# Speedometer_Drive_Board.net
KiCad netlist of a schematic drawn in EAGLE
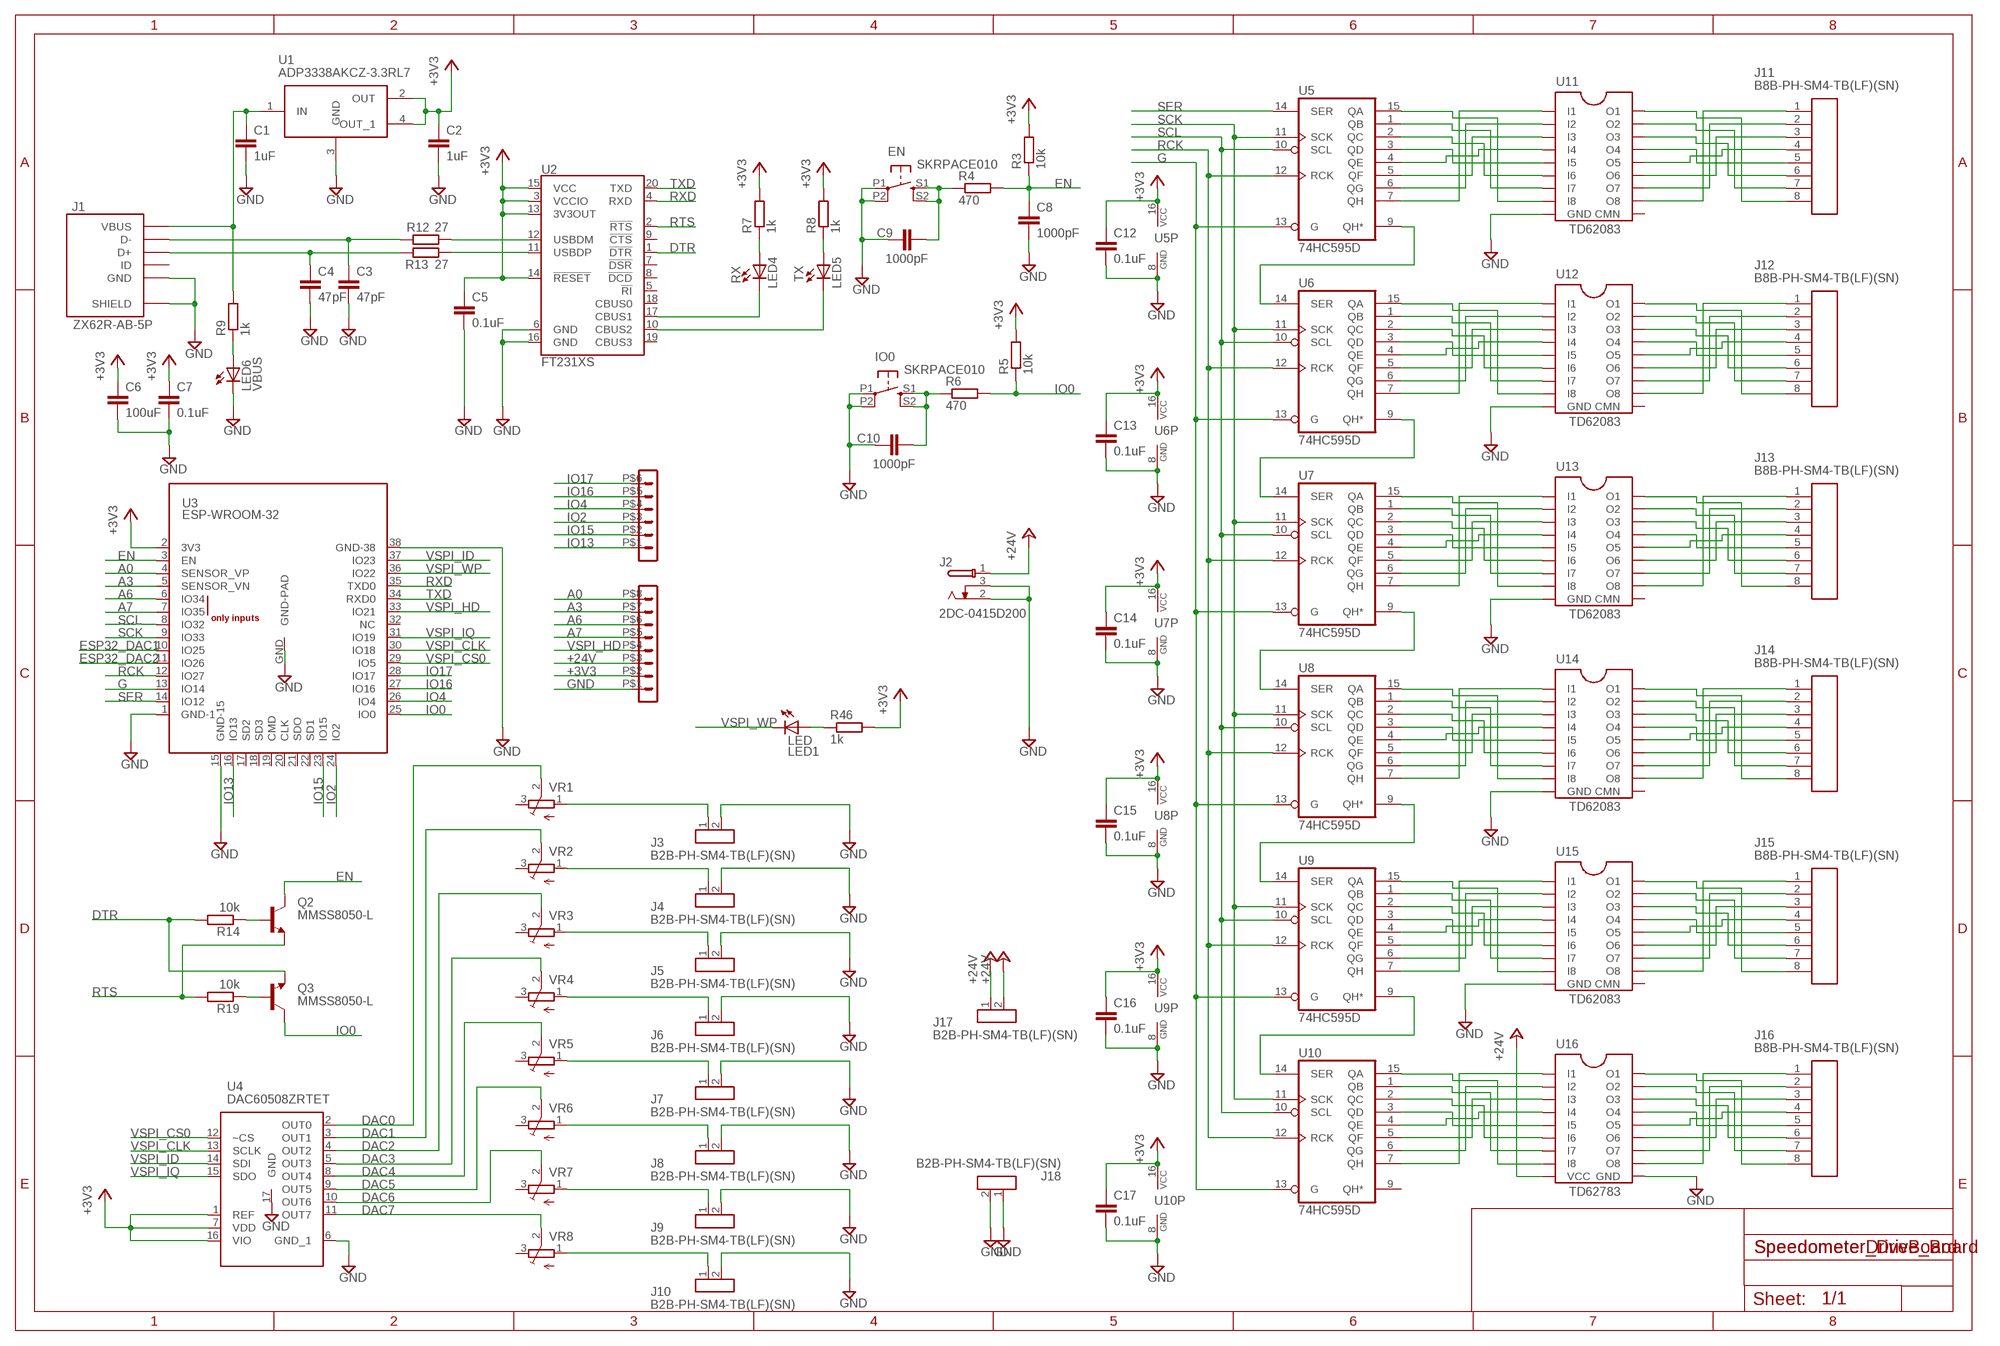
[diagram p0: schematic, sheet 1]

(export (version "E")
  (design (tool "Eeschema 10.0.6"))
  (components
    (comp (ref "C1")
      (value "1uF")
      (footprint "eagle-import:C0603")
      (libsource (lib "eagle-import") (part "C-EUC0603"))
    )
    (comp (ref "C2")
      (value "1uF")
      (footprint "eagle-import:C0603")
      (libsource (lib "eagle-import") (part "C-EUC0603"))
    )
    (comp (ref "C3")
      (value "47pF")
      (footprint "eagle-import:C0603")
      (libsource (lib "eagle-import") (part "C-EUC0603"))
    )
    (comp (ref "C4")
      (value "47pF")
      (footprint "eagle-import:C0603")
      (libsource (lib "eagle-import") (part "C-EUC0603"))
    )
    (comp (ref "C5")
      (value "0.1uF")
      (footprint "eagle-import:C0603")
      (libsource (lib "eagle-import") (part "C-EUC0603"))
    )
    (comp (ref "C6")
      (value "100uF")
      (footprint "eagle-import:C1210")
      (libsource (lib "eagle-import") (part "C-EUC1210"))
    )
    (comp (ref "C7")
      (value "0.1uF")
      (footprint "eagle-import:C0603")
      (libsource (lib "eagle-import") (part "C-EUC0603"))
    )
    (comp (ref "C8")
      (value "1000pF")
      (footprint "eagle-import:C0603")
      (libsource (lib "eagle-import") (part "C-EUC0603"))
    )
    (comp (ref "C9")
      (value "1000pF")
      (footprint "eagle-import:C0603")
      (libsource (lib "eagle-import") (part "C-EUC0603"))
    )
    (comp (ref "C10")
      (value "1000pF")
      (footprint "eagle-import:C0603")
      (libsource (lib "eagle-import") (part "C-EUC0603"))
    )
    (comp (ref "C12")
      (value "0.1uF")
      (footprint "eagle-import:C0603")
      (libsource (lib "eagle-import") (part "C-EUC0603"))
    )
    (comp (ref "C13")
      (value "0.1uF")
      (footprint "eagle-import:C0603")
      (libsource (lib "eagle-import") (part "C-EUC0603"))
    )
    (comp (ref "C14")
      (value "0.1uF")
      (footprint "eagle-import:C0603")
      (libsource (lib "eagle-import") (part "C-EUC0603"))
    )
    (comp (ref "C15")
      (value "0.1uF")
      (footprint "eagle-import:C0603")
      (libsource (lib "eagle-import") (part "C-EUC0603"))
    )
    (comp (ref "C16")
      (value "0.1uF")
      (footprint "eagle-import:C0603")
      (libsource (lib "eagle-import") (part "C-EUC0603"))
    )
    (comp (ref "C17")
      (value "0.1uF")
      (footprint "eagle-import:C0603")
      (libsource (lib "eagle-import") (part "C-EUC0603"))
    )
    (comp (ref "EN")
      (value "SKRPACE010")
      (footprint "eagle-import:SKRPACE010")
      (libsource (lib "eagle-import") (part "SKRPACE010"))
    )
    (comp (ref "IO0")
      (value "SKRPACE010")
      (footprint "eagle-import:SKRPACE010")
      (libsource (lib "eagle-import") (part "SKRPACE010"))
    )
    (comp (ref "J1")
      (value "ZX62R-AB-5P")
      (footprint "eagle-import:ZX62R-B-5PA")
      (libsource (lib "eagle-import") (part "ZX62R-AB-5P"))
    )
    (comp (ref "J2")
      (value "2DC-0415D200")
      (footprint "eagle-import:2DC-0415D200")
      (libsource (lib "eagle-import") (part "2DC-0415D200"))
    )
    (comp (ref "J3")
      (value "B2B-PH-SM4-TB(LF)(SN)")
      (footprint "eagle-import:SAMACSYS_PARTS_B2B-PH-SM4-TB")
      (fields (field (name "RS_PART_NUMBER") "6881325P"))
      (libsource (lib "eagle-import") (part "B2B-PH-SM4-TB(LF)(SN)"))
    )
    (comp (ref "J4")
      (value "B2B-PH-SM4-TB(LF)(SN)")
      (footprint "eagle-import:SAMACSYS_PARTS_B2B-PH-SM4-TB")
      (fields (field (name "RS_PART_NUMBER") "6881325P"))
      (libsource (lib "eagle-import") (part "B2B-PH-SM4-TB(LF)(SN)"))
    )
    (comp (ref "J5")
      (value "B2B-PH-SM4-TB(LF)(SN)")
      (footprint "eagle-import:SAMACSYS_PARTS_B2B-PH-SM4-TB")
      (fields (field (name "RS_PART_NUMBER") "6881325P"))
      (libsource (lib "eagle-import") (part "B2B-PH-SM4-TB(LF)(SN)"))
    )
    (comp (ref "J6")
      (value "B2B-PH-SM4-TB(LF)(SN)")
      (footprint "eagle-import:SAMACSYS_PARTS_B2B-PH-SM4-TB")
      (fields (field (name "RS_PART_NUMBER") "6881325P"))
      (libsource (lib "eagle-import") (part "B2B-PH-SM4-TB(LF)(SN)"))
    )
    (comp (ref "J7")
      (value "B2B-PH-SM4-TB(LF)(SN)")
      (footprint "eagle-import:SAMACSYS_PARTS_B2B-PH-SM4-TB")
      (fields (field (name "RS_PART_NUMBER") "6881325P"))
      (libsource (lib "eagle-import") (part "B2B-PH-SM4-TB(LF)(SN)"))
    )
    (comp (ref "J8")
      (value "B2B-PH-SM4-TB(LF)(SN)")
      (footprint "eagle-import:SAMACSYS_PARTS_B2B-PH-SM4-TB")
      (fields (field (name "RS_PART_NUMBER") "6881325P"))
      (libsource (lib "eagle-import") (part "B2B-PH-SM4-TB(LF)(SN)"))
    )
    (comp (ref "J9")
      (value "B2B-PH-SM4-TB(LF)(SN)")
      (footprint "eagle-import:SAMACSYS_PARTS_B2B-PH-SM4-TB")
      (fields (field (name "RS_PART_NUMBER") "6881325P"))
      (libsource (lib "eagle-import") (part "B2B-PH-SM4-TB(LF)(SN)"))
    )
    (comp (ref "J10")
      (value "B2B-PH-SM4-TB(LF)(SN)")
      (footprint "eagle-import:SAMACSYS_PARTS_B2B-PH-SM4-TB")
      (fields (field (name "RS_PART_NUMBER") "6881325P"))
      (libsource (lib "eagle-import") (part "B2B-PH-SM4-TB(LF)(SN)"))
    )
    (comp (ref "J11")
      (value "B8B-PH-SM4-TB(LF)(SN)")
      (footprint "eagle-import:SAMACSYS_PARTS_B8B-PH-SM4-TB")
      (fields (field (name "RS_PART_NUMBER") "1667263"))
      (libsource (lib "eagle-import") (part "B8B-PH-SM4-TB(LF)(SN)"))
    )
    (comp (ref "J12")
      (value "B8B-PH-SM4-TB(LF)(SN)")
      (footprint "eagle-import:SAMACSYS_PARTS_B8B-PH-SM4-TB")
      (fields (field (name "RS_PART_NUMBER") "1667263"))
      (libsource (lib "eagle-import") (part "B8B-PH-SM4-TB(LF)(SN)"))
    )
    (comp (ref "J13")
      (value "B8B-PH-SM4-TB(LF)(SN)")
      (footprint "eagle-import:SAMACSYS_PARTS_B8B-PH-SM4-TB")
      (fields (field (name "RS_PART_NUMBER") "1667263"))
      (libsource (lib "eagle-import") (part "B8B-PH-SM4-TB(LF)(SN)"))
    )
    (comp (ref "J14")
      (value "B8B-PH-SM4-TB(LF)(SN)")
      (footprint "eagle-import:SAMACSYS_PARTS_B8B-PH-SM4-TB")
      (fields (field (name "RS_PART_NUMBER") "1667263"))
      (libsource (lib "eagle-import") (part "B8B-PH-SM4-TB(LF)(SN)"))
    )
    (comp (ref "J15")
      (value "B8B-PH-SM4-TB(LF)(SN)")
      (footprint "eagle-import:SAMACSYS_PARTS_B8B-PH-SM4-TB")
      (fields (field (name "RS_PART_NUMBER") "1667263"))
      (libsource (lib "eagle-import") (part "B8B-PH-SM4-TB(LF)(SN)"))
    )
    (comp (ref "J16")
      (value "B8B-PH-SM4-TB(LF)(SN)")
      (footprint "eagle-import:SAMACSYS_PARTS_B8B-PH-SM4-TB")
      (fields (field (name "RS_PART_NUMBER") "1667263"))
      (libsource (lib "eagle-import") (part "B8B-PH-SM4-TB(LF)(SN)"))
    )
    (comp (ref "J17")
      (value "B2B-PH-SM4-TB(LF)(SN)")
      (footprint "eagle-import:SAMACSYS_PARTS_B2B-PH-SM4-TB")
      (fields (field (name "RS_PART_NUMBER") "6881325P"))
      (libsource (lib "eagle-import") (part "B2B-PH-SM4-TB(LF)(SN)"))
    )
    (comp (ref "J18")
      (value "B2B-PH-SM4-TB(LF)(SN)")
      (footprint "eagle-import:SAMACSYS_PARTS_B2B-PH-SM4-TB")
      (fields (field (name "RS_PART_NUMBER") "6881325P"))
      (libsource (lib "eagle-import") (part "B2B-PH-SM4-TB(LF)(SN)"))
    )
    (comp (ref "J19")
      (value "PIN_HEADER_MALE_1X06_06P")
      (footprint "eagle-import:PIN_HEADER_MALE_1X06_06P")
      (libsource (lib "eagle-import") (part "PIN_HEADER_MALE_1X06_06P"))
    )
    (comp (ref "J20")
      (value "PIN_HEADER_MALE_1X08_08P")
      (footprint "eagle-import:PIN_HEADER_MALE_1X08_08P")
      (libsource (lib "eagle-import") (part "PIN_HEADER_MALE_1X08_08P"))
    )
    (comp (ref "LED")
      (value "LED1")
      (footprint "eagle-import:CHIPLED_0603")
      (libsource (lib "eagle-import") (part "LEDCHIPLED_0603"))
    )
    (comp (ref "LED4")
      (value "RX")
      (footprint "eagle-import:CHIPLED_0603")
      (libsource (lib "eagle-import") (part "LEDCHIPLED_0603"))
    )
    (comp (ref "LED5")
      (value "TX")
      (footprint "eagle-import:CHIPLED_0603")
      (libsource (lib "eagle-import") (part "LEDCHIPLED_0603"))
    )
    (comp (ref "LED6")
      (value "VBUS")
      (footprint "eagle-import:CHIPLED_0603")
      (libsource (lib "eagle-import") (part "LEDCHIPLED_0603"))
    )
    (comp (ref "Q2")
      (value "MMSS8050-L")
      (footprint "eagle-import:SOT23")
      (libsource (lib "eagle-import") (part "MMSS8050-L"))
    )
    (comp (ref "Q3")
      (value "MMSS8050-L")
      (footprint "eagle-import:SOT23")
      (libsource (lib "eagle-import") (part "MMSS8050-L"))
    )
    (comp (ref "R3")
      (value "10k")
      (footprint "eagle-import:R0603")
      (libsource (lib "eagle-import") (part "R-EU_R0603"))
    )
    (comp (ref "R4")
      (value "470")
      (footprint "eagle-import:R0603")
      (libsource (lib "eagle-import") (part "R-EU_R0603"))
    )
    (comp (ref "R5")
      (value "10k")
      (footprint "eagle-import:R0603")
      (libsource (lib "eagle-import") (part "R-EU_R0603"))
    )
    (comp (ref "R6")
      (value "470")
      (footprint "eagle-import:R0603")
      (libsource (lib "eagle-import") (part "R-EU_R0603"))
    )
    (comp (ref "R7")
      (value "1k")
      (footprint "eagle-import:R0603")
      (libsource (lib "eagle-import") (part "R-EU_R0603"))
    )
    (comp (ref "R8")
      (value "1k")
      (footprint "eagle-import:R0603")
      (libsource (lib "eagle-import") (part "R-EU_R0603"))
    )
    (comp (ref "R9")
      (value "1k")
      (footprint "eagle-import:R0603")
      (libsource (lib "eagle-import") (part "R-EU_R0603"))
    )
    (comp (ref "R12")
      (value "27")
      (footprint "eagle-import:R0603")
      (libsource (lib "eagle-import") (part "R-EU_R0603"))
    )
    (comp (ref "R13")
      (value "27")
      (footprint "eagle-import:R0603")
      (libsource (lib "eagle-import") (part "R-EU_R0603"))
    )
    (comp (ref "R14")
      (value "10k")
      (footprint "eagle-import:R0603")
      (libsource (lib "eagle-import") (part "R-EU_R0603"))
    )
    (comp (ref "R19")
      (value "10k")
      (footprint "eagle-import:R0603")
      (libsource (lib "eagle-import") (part "R-EU_R0603"))
    )
    (comp (ref "R46")
      (value "1k")
      (footprint "eagle-import:R0603")
      (libsource (lib "eagle-import") (part "R-EU_R0603"))
    )
    (comp (ref "U1")
      (value "ADP3338AKCZ-3.3RL7")
      (footprint "eagle-import:SOT230P700X180-4N")
      (fields (field (name "RS_PART_NUMBER") "9126350"))
      (libsource (lib "eagle-import") (part "ADP3338AKCZ-3.3RL7"))
    )
    (comp (ref "U2")
      (value "FT231XS")
      (footprint "eagle-import:SSOP20_L")
      (libsource (lib "eagle-import") (part "FT231XS"))
    )
    (comp (ref "U3")
      (value "ESP-WROOM-32")
      (footprint "eagle-import:ESP-WROOM-32")
      (libsource (lib "eagle-import") (part "ESP-WROOM-32"))
    )
    (comp (ref "U4")
      (value "DAC60508ZRTET")
      (footprint "eagle-import:SAMACSYS_PARTS_QFN50P300X300X80-17N")
      (fields (field (name "MOUSER_PART_NUMBER") "595-DAC60508ZRTET"))
      (libsource (lib "eagle-import") (part "DAC60508ZRTET"))
    )
    (comp (ref "U5")
      (value "74HC595D")
      (footprint "eagle-import:SO16")
      (libsource (lib "eagle-import") (part "74595DHC"))
    )
    (comp (ref "U6")
      (value "74HC595D")
      (footprint "eagle-import:SO16")
      (libsource (lib "eagle-import") (part "74595DHC"))
    )
    (comp (ref "U7")
      (value "74HC595D")
      (footprint "eagle-import:SO16")
      (libsource (lib "eagle-import") (part "74595DHC"))
    )
    (comp (ref "U8")
      (value "74HC595D")
      (footprint "eagle-import:SO16")
      (libsource (lib "eagle-import") (part "74595DHC"))
    )
    (comp (ref "U9")
      (value "74HC595D")
      (footprint "eagle-import:SO16")
      (libsource (lib "eagle-import") (part "74595DHC"))
    )
    (comp (ref "U10")
      (value "74HC595D")
      (footprint "eagle-import:SO16")
      (libsource (lib "eagle-import") (part "74595DHC"))
    )
    (comp (ref "U11")
      (value "TD62083")
      (footprint "eagle-import:SO18")
      (libsource (lib "eagle-import") (part "TD62083"))
    )
    (comp (ref "U12")
      (value "TD62083")
      (footprint "eagle-import:SO18")
      (libsource (lib "eagle-import") (part "TD62083"))
    )
    (comp (ref "U13")
      (value "TD62083")
      (footprint "eagle-import:SO18")
      (libsource (lib "eagle-import") (part "TD62083"))
    )
    (comp (ref "U14")
      (value "TD62083")
      (footprint "eagle-import:SO18")
      (libsource (lib "eagle-import") (part "TD62083"))
    )
    (comp (ref "U15")
      (value "TD62083")
      (footprint "eagle-import:SO18")
      (libsource (lib "eagle-import") (part "TD62083"))
    )
    (comp (ref "U16")
      (value "TD62783")
      (footprint "eagle-import:SO18")
      (libsource (lib "eagle-import") (part "TD62783"))
    )
    (comp (ref "VR1")
      (value "TRIM_EU-SM-42/43W")
      (footprint "eagle-import:SM-42_43W")
      (libsource (lib "eagle-import") (part "TRIM_EU-SM-42/43W"))
    )
    (comp (ref "VR2")
      (value "TRIM_EU-SM-42/43W")
      (footprint "eagle-import:SM-42_43W")
      (libsource (lib "eagle-import") (part "TRIM_EU-SM-42/43W"))
    )
    (comp (ref "VR3")
      (value "TRIM_EU-SM-42/43W")
      (footprint "eagle-import:SM-42_43W")
      (libsource (lib "eagle-import") (part "TRIM_EU-SM-42/43W"))
    )
    (comp (ref "VR4")
      (value "TRIM_EU-SM-42/43W")
      (footprint "eagle-import:SM-42_43W")
      (libsource (lib "eagle-import") (part "TRIM_EU-SM-42/43W"))
    )
    (comp (ref "VR5")
      (value "TRIM_EU-SM-42/43W")
      (footprint "eagle-import:SM-42_43W")
      (libsource (lib "eagle-import") (part "TRIM_EU-SM-42/43W"))
    )
    (comp (ref "VR6")
      (value "TRIM_EU-SM-42/43W")
      (footprint "eagle-import:SM-42_43W")
      (libsource (lib "eagle-import") (part "TRIM_EU-SM-42/43W"))
    )
    (comp (ref "VR7")
      (value "TRIM_EU-SM-42/43W")
      (footprint "eagle-import:SM-42_43W")
      (libsource (lib "eagle-import") (part "TRIM_EU-SM-42/43W"))
    )
    (comp (ref "VR8")
      (value "TRIM_EU-SM-42/43W")
      (footprint "eagle-import:SM-42_43W")
      (libsource (lib "eagle-import") (part "TRIM_EU-SM-42/43W"))
    )
  )
  (nets
    (net (code "1") (name "+3V3") (class "Default")
      (node (ref "C12") (pin "1") (pinfunction "1_1") (pintype "passive"))
      (node (ref "C13") (pin "1") (pinfunction "1_1") (pintype "passive"))
      (node (ref "C14") (pin "1") (pinfunction "1_1") (pintype "passive"))
      (node (ref "C15") (pin "1") (pinfunction "1_1") (pintype "passive"))
      (node (ref "C16") (pin "1") (pinfunction "1_1") (pintype "passive"))
      (node (ref "C17") (pin "1") (pinfunction "1_1") (pintype "passive"))
      (node (ref "C2") (pin "1") (pinfunction "1_1") (pintype "passive"))
      (node (ref "C5") (pin "1") (pinfunction "1_1") (pintype "passive"))
      (node (ref "C6") (pin "1") (pinfunction "1_1") (pintype "passive"))
      (node (ref "C7") (pin "1") (pinfunction "1_1") (pintype "passive"))
      (node (ref "J20") (pin "P$2") (pinfunction "2_P$2") (pintype "bidirectional"))
      (node (ref "R3") (pin "2") (pinfunction "2_2") (pintype "passive"))
      (node (ref "R46") (pin "2") (pinfunction "2_2") (pintype "passive"))
      (node (ref "R5") (pin "2") (pinfunction "2_2") (pintype "passive"))
      (node (ref "R7") (pin "2") (pinfunction "2_2") (pintype "passive"))
      (node (ref "R8") (pin "2") (pinfunction "2_2") (pintype "passive"))
      (node (ref "U1") (pin "2") (pinfunction "OUT_2") (pintype "output"))
      (node (ref "U1") (pin "4") (pinfunction "OUT_1_4") (pintype "output"))
      (node (ref "U10") (pin "16") (pinfunction "VCC_16") (pintype "power_in"))
      (node (ref "U2") (pin "13") (pinfunction "3V3OUT_13") (pintype "bidirectional"))
      (node (ref "U2") (pin "14") (pinfunction "~{RESET}_14") (pintype "bidirectional"))
      (node (ref "U2") (pin "15") (pinfunction "VCC_15") (pintype "bidirectional"))
      (node (ref "U2") (pin "3") (pinfunction "VCCIO_3") (pintype "bidirectional"))
      (node (ref "U3") (pin "2") (pinfunction "3V3_2") (pintype "bidirectional"))
      (node (ref "U4") (pin "1") (pinfunction "REF_1") (pintype "bidirectional"))
      (node (ref "U4") (pin "16") (pinfunction "VIO_16") (pintype "bidirectional"))
      (node (ref "U4") (pin "7") (pinfunction "VDD_7") (pintype "bidirectional"))
      (node (ref "U5") (pin "16") (pinfunction "VCC_16") (pintype "power_in"))
      (node (ref "U6") (pin "16") (pinfunction "VCC_16") (pintype "power_in"))
      (node (ref "U7") (pin "16") (pinfunction "VCC_16") (pintype "power_in"))
      (node (ref "U8") (pin "16") (pinfunction "VCC_16") (pintype "power_in"))
      (node (ref "U9") (pin "16") (pinfunction "VCC_16") (pintype "power_in"))
    )
    (net (code "2") (name "+24V") (class "Default")
      (node (ref "J17") (pin "1") (pinfunction "P$1_1") (pintype "bidirectional"))
      (node (ref "J17") (pin "2") (pinfunction "P$2_2") (pintype "bidirectional"))
      (node (ref "J2") (pin "1") (pinfunction "1_1") (pintype "passive"))
      (node (ref "J20") (pin "P$3") (pinfunction "3_P$3") (pintype "bidirectional"))
      (node (ref "U16") (pin "9") (pinfunction "VCC_9") (pintype "passive"))
    )
    (net (code "3") (name "/A0") (class "Default")
      (node (ref "J20") (pin "P$8") (pinfunction "8_P$8") (pintype "bidirectional"))
      (node (ref "U3") (pin "4") (pinfunction "SENSOR_VP_4") (pintype "input"))
    )
    (net (code "4") (name "/A3") (class "Default")
      (node (ref "J20") (pin "P$7") (pinfunction "7_P$7") (pintype "bidirectional"))
      (node (ref "U3") (pin "5") (pinfunction "SENSOR_VN_5") (pintype "input"))
    )
    (net (code "5") (name "/A6") (class "Default")
      (node (ref "J20") (pin "P$6") (pinfunction "6_P$6") (pintype "bidirectional"))
      (node (ref "U3") (pin "6") (pinfunction "IO34_6") (pintype "input"))
    )
    (net (code "6") (name "/A7") (class "Default")
      (node (ref "J20") (pin "P$5") (pinfunction "5_P$5") (pintype "bidirectional"))
      (node (ref "U3") (pin "7") (pinfunction "IO35_7") (pintype "input"))
    )
    (net (code "7") (name "/DAC0") (class "Default")
      (node (ref "U4") (pin "2") (pinfunction "OUT0_2") (pintype "bidirectional"))
      (node (ref "VR1") (pin "2") (pinfunction "S_2") (pintype "passive"))
    )
    (net (code "8") (name "/DAC1") (class "Default")
      (node (ref "U4") (pin "3") (pinfunction "OUT1_3") (pintype "bidirectional"))
      (node (ref "VR2") (pin "2") (pinfunction "S_2") (pintype "passive"))
    )
    (net (code "9") (name "/DAC2") (class "Default")
      (node (ref "U4") (pin "4") (pinfunction "OUT2_4") (pintype "bidirectional"))
      (node (ref "VR3") (pin "2") (pinfunction "S_2") (pintype "passive"))
    )
    (net (code "10") (name "/DAC3") (class "Default")
      (node (ref "U4") (pin "5") (pinfunction "OUT3_5") (pintype "bidirectional"))
      (node (ref "VR4") (pin "2") (pinfunction "S_2") (pintype "passive"))
    )
    (net (code "11") (name "/DAC4") (class "Default")
      (node (ref "U4") (pin "8") (pinfunction "OUT4_8") (pintype "bidirectional"))
      (node (ref "VR5") (pin "2") (pinfunction "S_2") (pintype "passive"))
    )
    (net (code "12") (name "/DAC5") (class "Default")
      (node (ref "U4") (pin "9") (pinfunction "OUT5_9") (pintype "bidirectional"))
      (node (ref "VR6") (pin "2") (pinfunction "S_2") (pintype "passive"))
    )
    (net (code "13") (name "/DAC6") (class "Default")
      (node (ref "U4") (pin "10") (pinfunction "OUT6_10") (pintype "bidirectional"))
      (node (ref "VR7") (pin "2") (pinfunction "S_2") (pintype "passive"))
    )
    (net (code "14") (name "/DAC7") (class "Default")
      (node (ref "U4") (pin "11") (pinfunction "OUT7_11") (pintype "bidirectional"))
      (node (ref "VR8") (pin "2") (pinfunction "S_2") (pintype "passive"))
    )
    (net (code "15") (name "/DTR") (class "Default")
      (node (ref "Q3") (pin "E") (pinfunction "E_E") (pintype "passive"))
      (node (ref "R14") (pin "2") (pinfunction "2_2") (pintype "passive"))
      (node (ref "U2") (pin "1") (pinfunction "~{DTR}_1") (pintype "bidirectional"))
    )
    (net (code "16") (name "/EN") (class "Default")
      (node (ref "C8") (pin "1") (pinfunction "1_1") (pintype "passive"))
      (node (ref "Q2") (pin "C") (pinfunction "C_C") (pintype "passive"))
      (node (ref "R3") (pin "1") (pinfunction "1_1") (pintype "passive"))
      (node (ref "R4") (pin "2") (pinfunction "2_2") (pintype "passive"))
      (node (ref "U3") (pin "3") (pinfunction "EN_3") (pintype "bidirectional"))
    )
    (net (code "17") (name "/ESP32_DAC1") (class "Default")
      (node (ref "U3") (pin "10") (pinfunction "IO25_10") (pintype "bidirectional"))
    )
    (net (code "18") (name "/ESP32_DAC2") (class "Default")
      (node (ref "U3") (pin "11") (pinfunction "IO26_11") (pintype "bidirectional"))
    )
    (net (code "19") (name "/G") (class "Default")
      (node (ref "U10") (pin "13") (pinfunction "G_13") (pintype "input"))
      (node (ref "U3") (pin "13") (pinfunction "IO14_13") (pintype "bidirectional"))
      (node (ref "U5") (pin "13") (pinfunction "G_13") (pintype "input"))
      (node (ref "U6") (pin "13") (pinfunction "G_13") (pintype "input"))
      (node (ref "U7") (pin "13") (pinfunction "G_13") (pintype "input"))
      (node (ref "U8") (pin "13") (pinfunction "G_13") (pintype "input"))
      (node (ref "U9") (pin "13") (pinfunction "G_13") (pintype "input"))
    )
    (net (code "20") (name "/IO0") (class "Default")
      (node (ref "Q3") (pin "C") (pinfunction "C_C") (pintype "passive"))
      (node (ref "R5") (pin "1") (pinfunction "1_1") (pintype "passive"))
      (node (ref "R6") (pin "2") (pinfunction "2_2") (pintype "passive"))
      (node (ref "U3") (pin "25") (pinfunction "IO0_25") (pintype "bidirectional"))
    )
    (net (code "21") (name "/IO2") (class "Default")
      (node (ref "J19") (pin "P$3") (pinfunction "3_P$3") (pintype "bidirectional"))
      (node (ref "U3") (pin "24") (pinfunction "IO2_24") (pintype "bidirectional"))
    )
    (net (code "22") (name "/IO4") (class "Default")
      (node (ref "J19") (pin "P$4") (pinfunction "4_P$4") (pintype "bidirectional"))
      (node (ref "U3") (pin "26") (pinfunction "IO4_26") (pintype "bidirectional"))
    )
    (net (code "23") (name "/IO13") (class "Default")
      (node (ref "J19") (pin "P$1") (pinfunction "1_P$1") (pintype "bidirectional"))
      (node (ref "U3") (pin "16") (pinfunction "IO13_16") (pintype "bidirectional"))
    )
    (net (code "24") (name "/IO15") (class "Default")
      (node (ref "J19") (pin "P$2") (pinfunction "2_P$2") (pintype "bidirectional"))
      (node (ref "U3") (pin "23") (pinfunction "IO15_23") (pintype "bidirectional"))
    )
    (net (code "25") (name "/IO16") (class "Default")
      (node (ref "J19") (pin "P$5") (pinfunction "5_P$5") (pintype "bidirectional"))
      (node (ref "U3") (pin "27") (pinfunction "IO16_27") (pintype "bidirectional"))
    )
    (net (code "26") (name "/IO17") (class "Default")
      (node (ref "J19") (pin "P$6") (pinfunction "6_P$6") (pintype "bidirectional"))
      (node (ref "U3") (pin "28") (pinfunction "IO17_28") (pintype "bidirectional"))
    )
    (net (code "27") (name "/RCK") (class "Default")
      (node (ref "U10") (pin "12") (pinfunction "RCK_12") (pintype "input"))
      (node (ref "U3") (pin "12") (pinfunction "IO27_12") (pintype "bidirectional"))
      (node (ref "U5") (pin "12") (pinfunction "RCK_12") (pintype "input"))
      (node (ref "U6") (pin "12") (pinfunction "RCK_12") (pintype "input"))
      (node (ref "U7") (pin "12") (pinfunction "RCK_12") (pintype "input"))
      (node (ref "U8") (pin "12") (pinfunction "RCK_12") (pintype "input"))
      (node (ref "U9") (pin "12") (pinfunction "RCK_12") (pintype "input"))
    )
    (net (code "28") (name "/RTS") (class "Default")
      (node (ref "Q2") (pin "E") (pinfunction "E_E") (pintype "passive"))
      (node (ref "R19") (pin "2") (pinfunction "2_2") (pintype "passive"))
      (node (ref "U2") (pin "2") (pinfunction "~{RTS}_2") (pintype "bidirectional"))
    )
    (net (code "29") (name "/RXD") (class "Default")
      (node (ref "U2") (pin "4") (pinfunction "RXD_4") (pintype "bidirectional"))
      (node (ref "U3") (pin "35") (pinfunction "TXD0_35") (pintype "bidirectional"))
    )
    (net (code "30") (name "/SCK") (class "Default")
      (node (ref "U10") (pin "11") (pinfunction "SCK_11") (pintype "input"))
      (node (ref "U3") (pin "9") (pinfunction "IO33_9") (pintype "bidirectional"))
      (node (ref "U5") (pin "11") (pinfunction "SCK_11") (pintype "input"))
      (node (ref "U6") (pin "11") (pinfunction "SCK_11") (pintype "input"))
      (node (ref "U7") (pin "11") (pinfunction "SCK_11") (pintype "input"))
      (node (ref "U8") (pin "11") (pinfunction "SCK_11") (pintype "input"))
      (node (ref "U9") (pin "11") (pinfunction "SCK_11") (pintype "input"))
    )
    (net (code "31") (name "/SCL") (class "Default")
      (node (ref "U10") (pin "10") (pinfunction "SCL_10") (pintype "input"))
      (node (ref "U3") (pin "8") (pinfunction "IO32_8") (pintype "bidirectional"))
      (node (ref "U5") (pin "10") (pinfunction "SCL_10") (pintype "input"))
      (node (ref "U6") (pin "10") (pinfunction "SCL_10") (pintype "input"))
      (node (ref "U7") (pin "10") (pinfunction "SCL_10") (pintype "input"))
      (node (ref "U8") (pin "10") (pinfunction "SCL_10") (pintype "input"))
      (node (ref "U9") (pin "10") (pinfunction "SCL_10") (pintype "input"))
    )
    (net (code "32") (name "/SER") (class "Default")
      (node (ref "U3") (pin "14") (pinfunction "IO12_14") (pintype "bidirectional"))
      (node (ref "U5") (pin "14") (pinfunction "SER_14") (pintype "input"))
    )
    (net (code "33") (name "/TXD") (class "Default")
      (node (ref "U2") (pin "20") (pinfunction "TXD_20") (pintype "bidirectional"))
      (node (ref "U3") (pin "34") (pinfunction "RXD0_34") (pintype "bidirectional"))
    )
    (net (code "34") (name "/VSPI_CLK") (class "Default")
      (node (ref "U3") (pin "30") (pinfunction "IO18_30") (pintype "bidirectional"))
      (node (ref "U4") (pin "13") (pinfunction "SCLK_13") (pintype "bidirectional"))
    )
    (net (code "35") (name "/VSPI_CS0") (class "Default")
      (node (ref "U3") (pin "29") (pinfunction "IO5_29") (pintype "bidirectional"))
      (node (ref "U4") (pin "12") (pinfunction "~{CS}_12") (pintype "bidirectional"))
    )
    (net (code "36") (name "/VSPI_HD") (class "Default")
      (node (ref "J20") (pin "P$4") (pinfunction "4_P$4") (pintype "bidirectional"))
      (node (ref "U3") (pin "33") (pinfunction "IO21_33") (pintype "bidirectional"))
    )
    (net (code "37") (name "/VSPI_ID") (class "Default")
      (node (ref "U3") (pin "37") (pinfunction "IO23_37") (pintype "bidirectional"))
      (node (ref "U4") (pin "14") (pinfunction "SDI_14") (pintype "bidirectional"))
    )
    (net (code "38") (name "/VSPI_IQ") (class "Default")
      (node (ref "U3") (pin "31") (pinfunction "IO19_31") (pintype "bidirectional"))
      (node (ref "U4") (pin "15") (pinfunction "SDO_15") (pintype "bidirectional"))
    )
    (net (code "39") (name "/VSPI_WP") (class "Default")
      (node (ref "LED") (pin "C") (pinfunction "C_C") (pintype "passive"))
      (node (ref "U3") (pin "36") (pinfunction "IO22_36") (pintype "bidirectional"))
    )
    (net (code "40") (name "GND") (class "Default")
      (node (ref "C1") (pin "2") (pinfunction "2_2") (pintype "passive"))
      (node (ref "C10") (pin "1") (pinfunction "1_1") (pintype "passive"))
      (node (ref "C12") (pin "2") (pinfunction "2_2") (pintype "passive"))
      (node (ref "C13") (pin "2") (pinfunction "2_2") (pintype "passive"))
      (node (ref "C14") (pin "2") (pinfunction "2_2") (pintype "passive"))
      (node (ref "C15") (pin "2") (pinfunction "2_2") (pintype "passive"))
      (node (ref "C16") (pin "2") (pinfunction "2_2") (pintype "passive"))
      (node (ref "C17") (pin "2") (pinfunction "2_2") (pintype "passive"))
      (node (ref "C2") (pin "2") (pinfunction "2_2") (pintype "passive"))
      (node (ref "C3") (pin "2") (pinfunction "2_2") (pintype "passive"))
      (node (ref "C4") (pin "2") (pinfunction "2_2") (pintype "passive"))
      (node (ref "C5") (pin "2") (pinfunction "2_2") (pintype "passive"))
      (node (ref "C6") (pin "2") (pinfunction "2_2") (pintype "passive"))
      (node (ref "C7") (pin "2") (pinfunction "2_2") (pintype "passive"))
      (node (ref "C8") (pin "2") (pinfunction "2_2") (pintype "passive"))
      (node (ref "C9") (pin "1") (pinfunction "1_1") (pintype "passive"))
      (node (ref "EN") (pin "P1") (pinfunction "P_P1") (pintype "passive"))
      (node (ref "EN") (pin "P2") (pinfunction "P1_P2") (pintype "passive"))
      (node (ref "IO0") (pin "P1") (pinfunction "P_P1") (pintype "passive"))
      (node (ref "IO0") (pin "P2") (pinfunction "P1_P2") (pintype "passive"))
      (node (ref "J1") (pin "GND") (pinfunction "GND_GND") (pintype "bidirectional"))
      (node (ref "J1") (pin "SHIELD@1") (pinfunction "SHIELD_SHIELD@1") (pintype "bidirectional"))
      (node (ref "J1") (pin "SHIELD@2") (pinfunction "SHIELD_SHIELD@2") (pintype "bidirectional"))
      (node (ref "J1") (pin "SHIELD@3") (pinfunction "SHIELD_SHIELD@3") (pintype "bidirectional"))
      (node (ref "J1") (pin "SHIELD@4") (pinfunction "SHIELD_SHIELD@4") (pintype "bidirectional"))
      (node (ref "J10") (pin "2") (pinfunction "P$2_2") (pintype "bidirectional"))
      (node (ref "J18") (pin "1") (pinfunction "P$1_1") (pintype "bidirectional"))
      (node (ref "J18") (pin "2") (pinfunction "P$2_2") (pintype "bidirectional"))
      (node (ref "J2") (pin "2") (pinfunction "2_2") (pintype "passive"))
      (node (ref "J2") (pin "3") (pinfunction "3_3") (pintype "passive"))
      (node (ref "J20") (pin "P$1") (pinfunction "1_P$1") (pintype "bidirectional"))
      (node (ref "J3") (pin "2") (pinfunction "P$2_2") (pintype "bidirectional"))
      (node (ref "J4") (pin "2") (pinfunction "P$2_2") (pintype "bidirectional"))
      (node (ref "J5") (pin "2") (pinfunction "P$2_2") (pintype "bidirectional"))
      (node (ref "J6") (pin "2") (pinfunction "P$2_2") (pintype "bidirectional"))
      (node (ref "J7") (pin "2") (pinfunction "P$2_2") (pintype "bidirectional"))
      (node (ref "J8") (pin "2") (pinfunction "P$2_2") (pintype "bidirectional"))
      (node (ref "J9") (pin "2") (pinfunction "P$2_2") (pintype "bidirectional"))
      (node (ref "LED6") (pin "C") (pinfunction "C_C") (pintype "passive"))
      (node (ref "U1") (pin "3") (pinfunction "GND_3") (pintype "power_in"))
      (node (ref "U10") (pin "8") (pinfunction "GND_8") (pintype "power_in"))
      (node (ref "U11") (pin "9") (pinfunction "GND_9") (pintype "passive"))
      (node (ref "U12") (pin "9") (pinfunction "GND_9") (pintype "passive"))
      (node (ref "U13") (pin "9") (pinfunction "GND_9") (pintype "passive"))
      (node (ref "U14") (pin "9") (pinfunction "GND_9") (pintype "passive"))
      (node (ref "U15") (pin "9") (pinfunction "GND_9") (pintype "passive"))
      (node (ref "U16") (pin "10") (pinfunction "GND_10") (pintype "passive"))
      (node (ref "U2") (pin "16") (pinfunction "GND_16") (pintype "bidirectional"))
      (node (ref "U2") (pin "6") (pinfunction "GND_6") (pintype "bidirectional"))
      (node (ref "U3") (pin "1") (pinfunction "GND-1_1") (pintype "bidirectional"))
      (node (ref "U3") (pin "15") (pinfunction "GND-15_15") (pintype "bidirectional"))
      (node (ref "U3") (pin "38") (pinfunction "GND-38_38") (pintype "bidirectional"))
      (node (ref "U3") (pin "GND") (pinfunction "GND-PAD_GND") (pintype "bidirectional"))
      (node (ref "U4") (pin "17") (pinfunction "GND_17") (pintype "bidirectional"))
      (node (ref "U4") (pin "6") (pinfunction "GND_1_6") (pintype "bidirectional"))
      (node (ref "U5") (pin "8") (pinfunction "GND_8") (pintype "power_in"))
      (node (ref "U6") (pin "8") (pinfunction "GND_8") (pintype "power_in"))
      (node (ref "U7") (pin "8") (pinfunction "GND_8") (pintype "power_in"))
      (node (ref "U8") (pin "8") (pinfunction "GND_8") (pintype "power_in"))
      (node (ref "U9") (pin "8") (pinfunction "GND_8") (pintype "power_in"))
    )
    (net (code "41") (name "Net-(C3-Pad1)") (class "Default")
      (node (ref "C3") (pin "1") (pinfunction "1_1") (pintype "passive"))
      (node (ref "J1") (pin "D-") (pinfunction "D-_D-") (pintype "bidirectional"))
      (node (ref "R12") (pin "1") (pinfunction "1_1") (pintype "passive"))
    )
    (net (code "42") (name "Net-(C4-Pad1)") (class "Default")
      (node (ref "C4") (pin "1") (pinfunction "1_1") (pintype "passive"))
      (node (ref "J1") (pin "D+") (pinfunction "D+_D+") (pintype "bidirectional"))
      (node (ref "R13") (pin "1") (pinfunction "1_1") (pintype "passive"))
    )
    (net (code "43") (name "Net-(EN-S)") (class "Default")
      (node (ref "C9") (pin "2") (pinfunction "2_2") (pintype "passive"))
      (node (ref "EN") (pin "S1") (pinfunction "S_S1") (pintype "passive"))
      (node (ref "EN") (pin "S2") (pinfunction "S1_S2") (pintype "passive"))
      (node (ref "R4") (pin "1") (pinfunction "1_1") (pintype "passive"))
    )
    (net (code "44") (name "Net-(IO0-S)") (class "Default")
      (node (ref "C10") (pin "2") (pinfunction "2_2") (pintype "passive"))
      (node (ref "IO0") (pin "S1") (pinfunction "S_S1") (pintype "passive"))
      (node (ref "IO0") (pin "S2") (pinfunction "S1_S2") (pintype "passive"))
      (node (ref "R6") (pin "1") (pinfunction "1_1") (pintype "passive"))
    )
    (net (code "45") (name "Net-(J1-VBUS)") (class "Default")
      (node (ref "C1") (pin "1") (pinfunction "1_1") (pintype "passive"))
      (node (ref "J1") (pin "VCC") (pinfunction "VBUS_VCC") (pintype "bidirectional"))
      (node (ref "R9") (pin "2") (pinfunction "2_2") (pintype "passive"))
      (node (ref "U1") (pin "1") (pinfunction "IN_1") (pintype "input"))
    )
    (net (code "46") (name "Net-(J3-P$1)") (class "Default")
      (node (ref "J3") (pin "1") (pinfunction "P$1_1") (pintype "bidirectional"))
      (node (ref "VR1") (pin "1") (pinfunction "A_1") (pintype "passive"))
    )
    (net (code "47") (name "Net-(J4-P$1)") (class "Default")
      (node (ref "J4") (pin "1") (pinfunction "P$1_1") (pintype "bidirectional"))
      (node (ref "VR2") (pin "1") (pinfunction "A_1") (pintype "passive"))
    )
    (net (code "48") (name "Net-(J5-P$1)") (class "Default")
      (node (ref "J5") (pin "1") (pinfunction "P$1_1") (pintype "bidirectional"))
      (node (ref "VR3") (pin "1") (pinfunction "A_1") (pintype "passive"))
    )
    (net (code "49") (name "Net-(J6-P$1)") (class "Default")
      (node (ref "J6") (pin "1") (pinfunction "P$1_1") (pintype "bidirectional"))
      (node (ref "VR4") (pin "1") (pinfunction "A_1") (pintype "passive"))
    )
    (net (code "50") (name "Net-(J7-P$1)") (class "Default")
      (node (ref "J7") (pin "1") (pinfunction "P$1_1") (pintype "bidirectional"))
      (node (ref "VR5") (pin "1") (pinfunction "A_1") (pintype "passive"))
    )
    (net (code "51") (name "Net-(J8-P$1)") (class "Default")
      (node (ref "J8") (pin "1") (pinfunction "P$1_1") (pintype "bidirectional"))
      (node (ref "VR6") (pin "1") (pinfunction "A_1") (pintype "passive"))
    )
    (net (code "52") (name "Net-(J9-P$1)") (class "Default")
      (node (ref "J9") (pin "1") (pinfunction "P$1_1") (pintype "bidirectional"))
      (node (ref "VR7") (pin "1") (pinfunction "A_1") (pintype "passive"))
    )
    (net (code "53") (name "Net-(J10-P$1)") (class "Default")
      (node (ref "J10") (pin "1") (pinfunction "P$1_1") (pintype "bidirectional"))
      (node (ref "VR8") (pin "1") (pinfunction "A_1") (pintype "passive"))
    )
    (net (code "54") (name "Net-(J11-S1)") (class "Default")
      (node (ref "J11") (pin "1") (pinfunction "S1_1") (pintype "bidirectional"))
      (node (ref "U11") (pin "11") (pinfunction "O8_11") (pintype "passive"))
    )
    (net (code "55") (name "Net-(J11-S2)") (class "Default")
      (node (ref "J11") (pin "2") (pinfunction "S2_2") (pintype "bidirectional"))
      (node (ref "U11") (pin "12") (pinfunction "O7_12") (pintype "passive"))
    )
    (net (code "56") (name "Net-(J11-S3)") (class "Default")
      (node (ref "J11") (pin "3") (pinfunction "S3_3") (pintype "bidirectional"))
      (node (ref "U11") (pin "13") (pinfunction "O6_13") (pintype "passive"))
    )
    (net (code "57") (name "Net-(J11-S4)") (class "Default")
      (node (ref "J11") (pin "4") (pinfunction "S4_4") (pintype "bidirectional"))
      (node (ref "U11") (pin "14") (pinfunction "O5_14") (pintype "passive"))
    )
    (net (code "58") (name "Net-(J11-S5)") (class "Default")
      (node (ref "J11") (pin "5") (pinfunction "S5_5") (pintype "bidirectional"))
      (node (ref "U11") (pin "15") (pinfunction "O4_15") (pintype "passive"))
    )
    (net (code "59") (name "Net-(J11-S6)") (class "Default")
      (node (ref "J11") (pin "6") (pinfunction "S6_6") (pintype "bidirectional"))
      (node (ref "U11") (pin "16") (pinfunction "O3_16") (pintype "passive"))
    )
    (net (code "60") (name "Net-(J11-S7)") (class "Default")
      (node (ref "J11") (pin "7") (pinfunction "S7_7") (pintype "bidirectional"))
      (node (ref "U11") (pin "17") (pinfunction "O2_17") (pintype "passive"))
    )
    (net (code "61") (name "Net-(J11-S8)") (class "Default")
      (node (ref "J11") (pin "8") (pinfunction "S8_8") (pintype "bidirectional"))
      (node (ref "U11") (pin "18") (pinfunction "O1_18") (pintype "passive"))
    )
    (net (code "62") (name "Net-(J12-S1)") (class "Default")
      (node (ref "J12") (pin "1") (pinfunction "S1_1") (pintype "bidirectional"))
      (node (ref "U12") (pin "11") (pinfunction "O8_11") (pintype "passive"))
    )
    (net (code "63") (name "Net-(J12-S2)") (class "Default")
      (node (ref "J12") (pin "2") (pinfunction "S2_2") (pintype "bidirectional"))
      (node (ref "U12") (pin "12") (pinfunction "O7_12") (pintype "passive"))
    )
    (net (code "64") (name "Net-(J12-S3)") (class "Default")
      (node (ref "J12") (pin "3") (pinfunction "S3_3") (pintype "bidirectional"))
      (node (ref "U12") (pin "13") (pinfunction "O6_13") (pintype "passive"))
    )
    (net (code "65") (name "Net-(J12-S4)") (class "Default")
      (node (ref "J12") (pin "4") (pinfunction "S4_4") (pintype "bidirectional"))
      (node (ref "U12") (pin "14") (pinfunction "O5_14") (pintype "passive"))
    )
    (net (code "66") (name "Net-(J12-S5)") (class "Default")
      (node (ref "J12") (pin "5") (pinfunction "S5_5") (pintype "bidirectional"))
      (node (ref "U12") (pin "15") (pinfunction "O4_15") (pintype "passive"))
    )
    (net (code "67") (name "Net-(J12-S6)") (class "Default")
      (node (ref "J12") (pin "6") (pinfunction "S6_6") (pintype "bidirectional"))
      (node (ref "U12") (pin "16") (pinfunction "O3_16") (pintype "passive"))
    )
    (net (code "68") (name "Net-(J12-S7)") (class "Default")
      (node (ref "J12") (pin "7") (pinfunction "S7_7") (pintype "bidirectional"))
      (node (ref "U12") (pin "17") (pinfunction "O2_17") (pintype "passive"))
    )
    (net (code "69") (name "Net-(J12-S8)") (class "Default")
      (node (ref "J12") (pin "8") (pinfunction "S8_8") (pintype "bidirectional"))
      (node (ref "U12") (pin "18") (pinfunction "O1_18") (pintype "passive"))
    )
    (net (code "70") (name "Net-(J13-S1)") (class "Default")
      (node (ref "J13") (pin "1") (pinfunction "S1_1") (pintype "bidirectional"))
      (node (ref "U13") (pin "11") (pinfunction "O8_11") (pintype "passive"))
    )
    (net (code "71") (name "Net-(J13-S2)") (class "Default")
      (node (ref "J13") (pin "2") (pinfunction "S2_2") (pintype "bidirectional"))
      (node (ref "U13") (pin "12") (pinfunction "O7_12") (pintype "passive"))
    )
    (net (code "72") (name "Net-(J13-S3)") (class "Default")
      (node (ref "J13") (pin "3") (pinfunction "S3_3") (pintype "bidirectional"))
      (node (ref "U13") (pin "13") (pinfunction "O6_13") (pintype "passive"))
    )
    (net (code "73") (name "Net-(J13-S4)") (class "Default")
      (node (ref "J13") (pin "4") (pinfunction "S4_4") (pintype "bidirectional"))
      (node (ref "U13") (pin "14") (pinfunction "O5_14") (pintype "passive"))
    )
    (net (code "74") (name "Net-(J13-S5)") (class "Default")
      (node (ref "J13") (pin "5") (pinfunction "S5_5") (pintype "bidirectional"))
      (node (ref "U13") (pin "15") (pinfunction "O4_15") (pintype "passive"))
    )
    (net (code "75") (name "Net-(J13-S6)") (class "Default")
      (node (ref "J13") (pin "6") (pinfunction "S6_6") (pintype "bidirectional"))
      (node (ref "U13") (pin "16") (pinfunction "O3_16") (pintype "passive"))
    )
    (net (code "76") (name "Net-(J13-S7)") (class "Default")
      (node (ref "J13") (pin "7") (pinfunction "S7_7") (pintype "bidirectional"))
      (node (ref "U13") (pin "17") (pinfunction "O2_17") (pintype "passive"))
    )
    (net (code "77") (name "Net-(J13-S8)") (class "Default")
      (node (ref "J13") (pin "8") (pinfunction "S8_8") (pintype "bidirectional"))
      (node (ref "U13") (pin "18") (pinfunction "O1_18") (pintype "passive"))
    )
    (net (code "78") (name "Net-(J14-S1)") (class "Default")
      (node (ref "J14") (pin "1") (pinfunction "S1_1") (pintype "bidirectional"))
      (node (ref "U14") (pin "11") (pinfunction "O8_11") (pintype "passive"))
    )
    (net (code "79") (name "Net-(J14-S2)") (class "Default")
      (node (ref "J14") (pin "2") (pinfunction "S2_2") (pintype "bidirectional"))
      (node (ref "U14") (pin "12") (pinfunction "O7_12") (pintype "passive"))
    )
    (net (code "80") (name "Net-(J14-S3)") (class "Default")
      (node (ref "J14") (pin "3") (pinfunction "S3_3") (pintype "bidirectional"))
      (node (ref "U14") (pin "13") (pinfunction "O6_13") (pintype "passive"))
    )
    (net (code "81") (name "Net-(J14-S4)") (class "Default")
      (node (ref "J14") (pin "4") (pinfunction "S4_4") (pintype "bidirectional"))
      (node (ref "U14") (pin "14") (pinfunction "O5_14") (pintype "passive"))
    )
    (net (code "82") (name "Net-(J14-S5)") (class "Default")
      (node (ref "J14") (pin "5") (pinfunction "S5_5") (pintype "bidirectional"))
      (node (ref "U14") (pin "15") (pinfunction "O4_15") (pintype "passive"))
    )
    (net (code "83") (name "Net-(J14-S6)") (class "Default")
      (node (ref "J14") (pin "6") (pinfunction "S6_6") (pintype "bidirectional"))
      (node (ref "U14") (pin "16") (pinfunction "O3_16") (pintype "passive"))
    )
    (net (code "84") (name "Net-(J14-S7)") (class "Default")
      (node (ref "J14") (pin "7") (pinfunction "S7_7") (pintype "bidirectional"))
      (node (ref "U14") (pin "17") (pinfunction "O2_17") (pintype "passive"))
    )
    (net (code "85") (name "Net-(J14-S8)") (class "Default")
      (node (ref "J14") (pin "8") (pinfunction "S8_8") (pintype "bidirectional"))
      (node (ref "U14") (pin "18") (pinfunction "O1_18") (pintype "passive"))
    )
    (net (code "86") (name "Net-(J15-S1)") (class "Default")
      (node (ref "J15") (pin "1") (pinfunction "S1_1") (pintype "bidirectional"))
      (node (ref "U15") (pin "11") (pinfunction "O8_11") (pintype "passive"))
    )
    (net (code "87") (name "Net-(J15-S2)") (class "Default")
      (node (ref "J15") (pin "2") (pinfunction "S2_2") (pintype "bidirectional"))
      (node (ref "U15") (pin "12") (pinfunction "O7_12") (pintype "passive"))
    )
    (net (code "88") (name "Net-(J15-S3)") (class "Default")
      (node (ref "J15") (pin "3") (pinfunction "S3_3") (pintype "bidirectional"))
      (node (ref "U15") (pin "13") (pinfunction "O6_13") (pintype "passive"))
    )
    (net (code "89") (name "Net-(J15-S4)") (class "Default")
      (node (ref "J15") (pin "4") (pinfunction "S4_4") (pintype "bidirectional"))
      (node (ref "U15") (pin "14") (pinfunction "O5_14") (pintype "passive"))
    )
    (net (code "90") (name "Net-(J15-S5)") (class "Default")
      (node (ref "J15") (pin "5") (pinfunction "S5_5") (pintype "bidirectional"))
      (node (ref "U15") (pin "15") (pinfunction "O4_15") (pintype "passive"))
    )
    (net (code "91") (name "Net-(J15-S6)") (class "Default")
      (node (ref "J15") (pin "6") (pinfunction "S6_6") (pintype "bidirectional"))
      (node (ref "U15") (pin "16") (pinfunction "O3_16") (pintype "passive"))
    )
    (net (code "92") (name "Net-(J15-S7)") (class "Default")
      (node (ref "J15") (pin "7") (pinfunction "S7_7") (pintype "bidirectional"))
      (node (ref "U15") (pin "17") (pinfunction "O2_17") (pintype "passive"))
    )
    (net (code "93") (name "Net-(J15-S8)") (class "Default")
      (node (ref "J15") (pin "8") (pinfunction "S8_8") (pintype "bidirectional"))
      (node (ref "U15") (pin "18") (pinfunction "O1_18") (pintype "passive"))
    )
    (net (code "94") (name "Net-(J16-S1)") (class "Default")
      (node (ref "J16") (pin "1") (pinfunction "S1_1") (pintype "bidirectional"))
      (node (ref "U16") (pin "11") (pinfunction "O8_11") (pintype "passive"))
    )
    (net (code "95") (name "Net-(J16-S2)") (class "Default")
      (node (ref "J16") (pin "2") (pinfunction "S2_2") (pintype "bidirectional"))
      (node (ref "U16") (pin "12") (pinfunction "O7_12") (pintype "passive"))
    )
    (net (code "96") (name "Net-(J16-S3)") (class "Default")
      (node (ref "J16") (pin "3") (pinfunction "S3_3") (pintype "bidirectional"))
      (node (ref "U16") (pin "13") (pinfunction "O6_13") (pintype "passive"))
    )
    (net (code "97") (name "Net-(J16-S4)") (class "Default")
      (node (ref "J16") (pin "4") (pinfunction "S4_4") (pintype "bidirectional"))
      (node (ref "U16") (pin "14") (pinfunction "O5_14") (pintype "passive"))
    )
    (net (code "98") (name "Net-(J16-S5)") (class "Default")
      (node (ref "J16") (pin "5") (pinfunction "S5_5") (pintype "bidirectional"))
      (node (ref "U16") (pin "15") (pinfunction "O4_15") (pintype "passive"))
    )
    (net (code "99") (name "Net-(J16-S6)") (class "Default")
      (node (ref "J16") (pin "6") (pinfunction "S6_6") (pintype "bidirectional"))
      (node (ref "U16") (pin "16") (pinfunction "O3_16") (pintype "passive"))
    )
    (net (code "100") (name "Net-(J16-S7)") (class "Default")
      (node (ref "J16") (pin "7") (pinfunction "S7_7") (pintype "bidirectional"))
      (node (ref "U16") (pin "17") (pinfunction "O2_17") (pintype "passive"))
    )
    (net (code "101") (name "Net-(J16-S8)") (class "Default")
      (node (ref "J16") (pin "8") (pinfunction "S8_8") (pintype "bidirectional"))
      (node (ref "U16") (pin "18") (pinfunction "O1_18") (pintype "passive"))
    )
    (net (code "102") (name "Net-(LED-PadA)") (class "Default")
      (node (ref "LED") (pin "A") (pinfunction "A_A") (pintype "passive"))
      (node (ref "R46") (pin "1") (pinfunction "1_1") (pintype "passive"))
    )
    (net (code "103") (name "Net-(LED4-PadA)") (class "Default")
      (node (ref "LED4") (pin "A") (pinfunction "A_A") (pintype "passive"))
      (node (ref "R7") (pin "1") (pinfunction "1_1") (pintype "passive"))
    )
    (net (code "104") (name "Net-(LED5-PadA)") (class "Default")
      (node (ref "LED5") (pin "A") (pinfunction "A_A") (pintype "passive"))
      (node (ref "R8") (pin "1") (pinfunction "1_1") (pintype "passive"))
    )
    (net (code "105") (name "Net-(LED6-PadA)") (class "Default")
      (node (ref "LED6") (pin "A") (pinfunction "A_A") (pintype "passive"))
      (node (ref "R9") (pin "1") (pinfunction "1_1") (pintype "passive"))
    )
    (net (code "106") (name "Net-(Q2-PadB)") (class "Default")
      (node (ref "Q2") (pin "B") (pinfunction "B_B") (pintype "passive"))
      (node (ref "R14") (pin "1") (pinfunction "1_1") (pintype "passive"))
    )
    (net (code "107") (name "Net-(Q3-PadB)") (class "Default")
      (node (ref "Q3") (pin "B") (pinfunction "B_B") (pintype "passive"))
      (node (ref "R19") (pin "1") (pinfunction "1_1") (pintype "passive"))
    )
    (net (code "108") (name "Net-(U2-CBUS1)") (class "Default")
      (node (ref "LED4") (pin "C") (pinfunction "C_C") (pintype "passive"))
      (node (ref "U2") (pin "17") (pinfunction "CBUS1_17") (pintype "bidirectional"))
    )
    (net (code "109") (name "Net-(U2-CBUS2)") (class "Default")
      (node (ref "LED5") (pin "C") (pinfunction "C_C") (pintype "passive"))
      (node (ref "U2") (pin "10") (pinfunction "CBUS2_10") (pintype "bidirectional"))
    )
    (net (code "110") (name "Net-(U2-USBDM)") (class "Default")
      (node (ref "R12") (pin "2") (pinfunction "2_2") (pintype "passive"))
      (node (ref "U2") (pin "12") (pinfunction "USBDM_12") (pintype "bidirectional"))
    )
    (net (code "111") (name "Net-(U2-USBDP)") (class "Default")
      (node (ref "R13") (pin "2") (pinfunction "2_2") (pintype "passive"))
      (node (ref "U2") (pin "11") (pinfunction "USBDP_11") (pintype "bidirectional"))
    )
    (net (code "112") (name "Net-(U5A-QH*)") (class "Default")
      (node (ref "U5") (pin "9") (pinfunction "QH*_9") (pintype "tri_state"))
      (node (ref "U6") (pin "14") (pinfunction "SER_14") (pintype "input"))
    )
    (net (code "113") (name "Net-(U6A-QH*)") (class "Default")
      (node (ref "U6") (pin "9") (pinfunction "QH*_9") (pintype "tri_state"))
      (node (ref "U7") (pin "14") (pinfunction "SER_14") (pintype "input"))
    )
    (net (code "114") (name "Net-(U7A-QH*)") (class "Default")
      (node (ref "U7") (pin "9") (pinfunction "QH*_9") (pintype "tri_state"))
      (node (ref "U8") (pin "14") (pinfunction "SER_14") (pintype "input"))
    )
    (net (code "115") (name "Net-(U8A-QH*)") (class "Default")
      (node (ref "U8") (pin "9") (pinfunction "QH*_9") (pintype "tri_state"))
      (node (ref "U9") (pin "14") (pinfunction "SER_14") (pintype "input"))
    )
    (net (code "116") (name "Net-(U10A-QA)") (class "Default")
      (node (ref "U10") (pin "15") (pinfunction "QA_15") (pintype "tri_state"))
      (node (ref "U16") (pin "8") (pinfunction "I8_8") (pintype "passive"))
    )
    (net (code "117") (name "Net-(U10A-QB)") (class "Default")
      (node (ref "U10") (pin "1") (pinfunction "QB_1") (pintype "tri_state"))
      (node (ref "U16") (pin "7") (pinfunction "I7_7") (pintype "passive"))
    )
    (net (code "118") (name "Net-(U10A-QC)") (class "Default")
      (node (ref "U10") (pin "2") (pinfunction "QC_2") (pintype "tri_state"))
      (node (ref "U16") (pin "6") (pinfunction "I6_6") (pintype "passive"))
    )
    (net (code "119") (name "Net-(U10A-QD)") (class "Default")
      (node (ref "U10") (pin "3") (pinfunction "QD_3") (pintype "tri_state"))
      (node (ref "U16") (pin "5") (pinfunction "I5_5") (pintype "passive"))
    )
    (net (code "120") (name "Net-(U10A-QE)") (class "Default")
      (node (ref "U10") (pin "4") (pinfunction "QE_4") (pintype "tri_state"))
      (node (ref "U16") (pin "4") (pinfunction "I4_4") (pintype "passive"))
    )
    (net (code "121") (name "Net-(U10A-QF)") (class "Default")
      (node (ref "U10") (pin "5") (pinfunction "QF_5") (pintype "tri_state"))
      (node (ref "U16") (pin "3") (pinfunction "I3_3") (pintype "passive"))
    )
    (net (code "122") (name "Net-(U10A-QG)") (class "Default")
      (node (ref "U10") (pin "6") (pinfunction "QG_6") (pintype "tri_state"))
      (node (ref "U16") (pin "2") (pinfunction "I2_2") (pintype "passive"))
    )
    (net (code "123") (name "Net-(U10A-QH)") (class "Default")
      (node (ref "U10") (pin "7") (pinfunction "QH_7") (pintype "tri_state"))
      (node (ref "U16") (pin "1") (pinfunction "I1_1") (pintype "passive"))
    )
    (net (code "124") (name "Net-(U10A-SER)") (class "Default")
      (node (ref "U10") (pin "14") (pinfunction "SER_14") (pintype "input"))
      (node (ref "U9") (pin "9") (pinfunction "QH*_9") (pintype "tri_state"))
    )
    (net (code "125") (name "Net-(U11-I1)") (class "Default")
      (node (ref "U11") (pin "1") (pinfunction "I1_1") (pintype "passive"))
      (node (ref "U5") (pin "7") (pinfunction "QH_7") (pintype "tri_state"))
    )
    (net (code "126") (name "Net-(U11-I2)") (class "Default")
      (node (ref "U11") (pin "2") (pinfunction "I2_2") (pintype "passive"))
      (node (ref "U5") (pin "6") (pinfunction "QG_6") (pintype "tri_state"))
    )
    (net (code "127") (name "Net-(U11-I3)") (class "Default")
      (node (ref "U11") (pin "3") (pinfunction "I3_3") (pintype "passive"))
      (node (ref "U5") (pin "5") (pinfunction "QF_5") (pintype "tri_state"))
    )
    (net (code "128") (name "Net-(U11-I4)") (class "Default")
      (node (ref "U11") (pin "4") (pinfunction "I4_4") (pintype "passive"))
      (node (ref "U5") (pin "4") (pinfunction "QE_4") (pintype "tri_state"))
    )
    (net (code "129") (name "Net-(U11-I5)") (class "Default")
      (node (ref "U11") (pin "5") (pinfunction "I5_5") (pintype "passive"))
      (node (ref "U5") (pin "3") (pinfunction "QD_3") (pintype "tri_state"))
    )
    (net (code "130") (name "Net-(U11-I6)") (class "Default")
      (node (ref "U11") (pin "6") (pinfunction "I6_6") (pintype "passive"))
      (node (ref "U5") (pin "2") (pinfunction "QC_2") (pintype "tri_state"))
    )
    (net (code "131") (name "Net-(U11-I7)") (class "Default")
      (node (ref "U11") (pin "7") (pinfunction "I7_7") (pintype "passive"))
      (node (ref "U5") (pin "1") (pinfunction "QB_1") (pintype "tri_state"))
    )
    (net (code "132") (name "Net-(U11-I8)") (class "Default")
      (node (ref "U11") (pin "8") (pinfunction "I8_8") (pintype "passive"))
      (node (ref "U5") (pin "15") (pinfunction "QA_15") (pintype "tri_state"))
    )
    (net (code "133") (name "Net-(U12-I1)") (class "Default")
      (node (ref "U12") (pin "1") (pinfunction "I1_1") (pintype "passive"))
      (node (ref "U6") (pin "7") (pinfunction "QH_7") (pintype "tri_state"))
    )
    (net (code "134") (name "Net-(U12-I2)") (class "Default")
      (node (ref "U12") (pin "2") (pinfunction "I2_2") (pintype "passive"))
      (node (ref "U6") (pin "6") (pinfunction "QG_6") (pintype "tri_state"))
    )
    (net (code "135") (name "Net-(U12-I3)") (class "Default")
      (node (ref "U12") (pin "3") (pinfunction "I3_3") (pintype "passive"))
      (node (ref "U6") (pin "5") (pinfunction "QF_5") (pintype "tri_state"))
    )
    (net (code "136") (name "Net-(U12-I4)") (class "Default")
      (node (ref "U12") (pin "4") (pinfunction "I4_4") (pintype "passive"))
      (node (ref "U6") (pin "4") (pinfunction "QE_4") (pintype "tri_state"))
    )
    (net (code "137") (name "Net-(U12-I5)") (class "Default")
      (node (ref "U12") (pin "5") (pinfunction "I5_5") (pintype "passive"))
      (node (ref "U6") (pin "3") (pinfunction "QD_3") (pintype "tri_state"))
    )
    (net (code "138") (name "Net-(U12-I6)") (class "Default")
      (node (ref "U12") (pin "6") (pinfunction "I6_6") (pintype "passive"))
      (node (ref "U6") (pin "2") (pinfunction "QC_2") (pintype "tri_state"))
    )
    (net (code "139") (name "Net-(U12-I7)") (class "Default")
      (node (ref "U12") (pin "7") (pinfunction "I7_7") (pintype "passive"))
      (node (ref "U6") (pin "1") (pinfunction "QB_1") (pintype "tri_state"))
    )
    (net (code "140") (name "Net-(U12-I8)") (class "Default")
      (node (ref "U12") (pin "8") (pinfunction "I8_8") (pintype "passive"))
      (node (ref "U6") (pin "15") (pinfunction "QA_15") (pintype "tri_state"))
    )
    (net (code "141") (name "Net-(U13-I1)") (class "Default")
      (node (ref "U13") (pin "1") (pinfunction "I1_1") (pintype "passive"))
      (node (ref "U7") (pin "7") (pinfunction "QH_7") (pintype "tri_state"))
    )
    (net (code "142") (name "Net-(U13-I2)") (class "Default")
      (node (ref "U13") (pin "2") (pinfunction "I2_2") (pintype "passive"))
      (node (ref "U7") (pin "6") (pinfunction "QG_6") (pintype "tri_state"))
    )
    (net (code "143") (name "Net-(U13-I3)") (class "Default")
      (node (ref "U13") (pin "3") (pinfunction "I3_3") (pintype "passive"))
      (node (ref "U7") (pin "5") (pinfunction "QF_5") (pintype "tri_state"))
    )
    (net (code "144") (name "Net-(U13-I4)") (class "Default")
      (node (ref "U13") (pin "4") (pinfunction "I4_4") (pintype "passive"))
      (node (ref "U7") (pin "4") (pinfunction "QE_4") (pintype "tri_state"))
    )
    (net (code "145") (name "Net-(U13-I5)") (class "Default")
      (node (ref "U13") (pin "5") (pinfunction "I5_5") (pintype "passive"))
      (node (ref "U7") (pin "3") (pinfunction "QD_3") (pintype "tri_state"))
    )
    (net (code "146") (name "Net-(U13-I6)") (class "Default")
      (node (ref "U13") (pin "6") (pinfunction "I6_6") (pintype "passive"))
      (node (ref "U7") (pin "2") (pinfunction "QC_2") (pintype "tri_state"))
    )
    (net (code "147") (name "Net-(U13-I7)") (class "Default")
      (node (ref "U13") (pin "7") (pinfunction "I7_7") (pintype "passive"))
      (node (ref "U7") (pin "1") (pinfunction "QB_1") (pintype "tri_state"))
    )
    (net (code "148") (name "Net-(U13-I8)") (class "Default")
      (node (ref "U13") (pin "8") (pinfunction "I8_8") (pintype "passive"))
      (node (ref "U7") (pin "15") (pinfunction "QA_15") (pintype "tri_state"))
    )
    (net (code "149") (name "Net-(U14-I1)") (class "Default")
      (node (ref "U14") (pin "1") (pinfunction "I1_1") (pintype "passive"))
      (node (ref "U8") (pin "7") (pinfunction "QH_7") (pintype "tri_state"))
    )
    (net (code "150") (name "Net-(U14-I2)") (class "Default")
      (node (ref "U14") (pin "2") (pinfunction "I2_2") (pintype "passive"))
      (node (ref "U8") (pin "6") (pinfunction "QG_6") (pintype "tri_state"))
    )
    (net (code "151") (name "Net-(U14-I3)") (class "Default")
      (node (ref "U14") (pin "3") (pinfunction "I3_3") (pintype "passive"))
      (node (ref "U8") (pin "5") (pinfunction "QF_5") (pintype "tri_state"))
    )
    (net (code "152") (name "Net-(U14-I4)") (class "Default")
      (node (ref "U14") (pin "4") (pinfunction "I4_4") (pintype "passive"))
      (node (ref "U8") (pin "4") (pinfunction "QE_4") (pintype "tri_state"))
    )
    (net (code "153") (name "Net-(U14-I5)") (class "Default")
      (node (ref "U14") (pin "5") (pinfunction "I5_5") (pintype "passive"))
      (node (ref "U8") (pin "3") (pinfunction "QD_3") (pintype "tri_state"))
    )
    (net (code "154") (name "Net-(U14-I6)") (class "Default")
      (node (ref "U14") (pin "6") (pinfunction "I6_6") (pintype "passive"))
      (node (ref "U8") (pin "2") (pinfunction "QC_2") (pintype "tri_state"))
    )
    (net (code "155") (name "Net-(U14-I7)") (class "Default")
      (node (ref "U14") (pin "7") (pinfunction "I7_7") (pintype "passive"))
      (node (ref "U8") (pin "1") (pinfunction "QB_1") (pintype "tri_state"))
    )
    (net (code "156") (name "Net-(U14-I8)") (class "Default")
      (node (ref "U14") (pin "8") (pinfunction "I8_8") (pintype "passive"))
      (node (ref "U8") (pin "15") (pinfunction "QA_15") (pintype "tri_state"))
    )
    (net (code "157") (name "Net-(U15-I1)") (class "Default")
      (node (ref "U15") (pin "1") (pinfunction "I1_1") (pintype "passive"))
      (node (ref "U9") (pin "7") (pinfunction "QH_7") (pintype "tri_state"))
    )
    (net (code "158") (name "Net-(U15-I2)") (class "Default")
      (node (ref "U15") (pin "2") (pinfunction "I2_2") (pintype "passive"))
      (node (ref "U9") (pin "6") (pinfunction "QG_6") (pintype "tri_state"))
    )
    (net (code "159") (name "Net-(U15-I3)") (class "Default")
      (node (ref "U15") (pin "3") (pinfunction "I3_3") (pintype "passive"))
      (node (ref "U9") (pin "5") (pinfunction "QF_5") (pintype "tri_state"))
    )
    (net (code "160") (name "Net-(U15-I4)") (class "Default")
      (node (ref "U15") (pin "4") (pinfunction "I4_4") (pintype "passive"))
      (node (ref "U9") (pin "4") (pinfunction "QE_4") (pintype "tri_state"))
    )
    (net (code "161") (name "Net-(U15-I5)") (class "Default")
      (node (ref "U15") (pin "5") (pinfunction "I5_5") (pintype "passive"))
      (node (ref "U9") (pin "3") (pinfunction "QD_3") (pintype "tri_state"))
    )
    (net (code "162") (name "Net-(U15-I6)") (class "Default")
      (node (ref "U15") (pin "6") (pinfunction "I6_6") (pintype "passive"))
      (node (ref "U9") (pin "2") (pinfunction "QC_2") (pintype "tri_state"))
    )
    (net (code "163") (name "Net-(U15-I7)") (class "Default")
      (node (ref "U15") (pin "7") (pinfunction "I7_7") (pintype "passive"))
      (node (ref "U9") (pin "1") (pinfunction "QB_1") (pintype "tri_state"))
    )
    (net (code "164") (name "Net-(U15-I8)") (class "Default")
      (node (ref "U15") (pin "8") (pinfunction "I8_8") (pintype "passive"))
      (node (ref "U9") (pin "15") (pinfunction "QA_15") (pintype "tri_state"))
    )
    (net (code "165") (name "unconnected-(J1-PadID)") (class "Default")
      (node (ref "J1") (pin "ID") (pinfunction "ID_ID") (pintype "bidirectional"))
    )
    (net (code "166") (name "unconnected-(U2-CBUS0-Pad18)") (class "Default")
      (node (ref "U2") (pin "18") (pinfunction "CBUS0_18") (pintype "bidirectional"))
    )
    (net (code "167") (name "unconnected-(U2-CBUS3-Pad19)") (class "Default")
      (node (ref "U2") (pin "19") (pinfunction "CBUS3_19") (pintype "bidirectional"))
    )
    (net (code "168") (name "unconnected-(U2-~{CTS}-Pad9)") (class "Default")
      (node (ref "U2") (pin "9") (pinfunction "~{CTS}_9") (pintype "bidirectional"))
    )
    (net (code "169") (name "unconnected-(U2-~{DCD}-Pad8)") (class "Default")
      (node (ref "U2") (pin "8") (pinfunction "~{DCD}_8") (pintype "bidirectional"))
    )
    (net (code "170") (name "unconnected-(U2-~{DSR}-Pad7)") (class "Default")
      (node (ref "U2") (pin "7") (pinfunction "~{DSR}_7") (pintype "bidirectional"))
    )
    (net (code "171") (name "unconnected-(U2-~{RI}-Pad5)") (class "Default")
      (node (ref "U2") (pin "5") (pinfunction "~{RI}_5") (pintype "bidirectional"))
    )
    (net (code "172") (name "unconnected-(U3-CLK-Pad20)") (class "Default")
      (node (ref "U3") (pin "20") (pinfunction "CLK_20") (pintype "bidirectional"))
    )
    (net (code "173") (name "unconnected-(U3-CMD-Pad19)") (class "Default")
      (node (ref "U3") (pin "19") (pinfunction "CMD_19") (pintype "bidirectional"))
    )
    (net (code "174") (name "unconnected-(U3-NC-Pad32)") (class "Default")
      (node (ref "U3") (pin "32") (pinfunction "NC_32") (pintype "bidirectional"))
    )
    (net (code "175") (name "unconnected-(U3-SD1-Pad22)") (class "Default")
      (node (ref "U3") (pin "22") (pinfunction "SD1_22") (pintype "bidirectional"))
    )
    (net (code "176") (name "unconnected-(U3-SD2-Pad17)") (class "Default")
      (node (ref "U3") (pin "17") (pinfunction "SD2_17") (pintype "bidirectional"))
    )
    (net (code "177") (name "unconnected-(U3-SD3-Pad18)") (class "Default")
      (node (ref "U3") (pin "18") (pinfunction "SD3_18") (pintype "bidirectional"))
    )
    (net (code "178") (name "unconnected-(U3-SDO-Pad21)") (class "Default")
      (node (ref "U3") (pin "21") (pinfunction "SDO_21") (pintype "bidirectional"))
    )
    (net (code "179") (name "unconnected-(U10A-QH*-Pad9)") (class "Default")
      (node (ref "U10") (pin "9") (pinfunction "QH*_9") (pintype "tri_state"))
    )
    (net (code "180") (name "unconnected-(U11-CMN-Pad10)") (class "Default")
      (node (ref "U11") (pin "10") (pinfunction "CMN_10") (pintype "passive"))
    )
    (net (code "181") (name "unconnected-(U12-CMN-Pad10)") (class "Default")
      (node (ref "U12") (pin "10") (pinfunction "CMN_10") (pintype "passive"))
    )
    (net (code "182") (name "unconnected-(U13-CMN-Pad10)") (class "Default")
      (node (ref "U13") (pin "10") (pinfunction "CMN_10") (pintype "passive"))
    )
    (net (code "183") (name "unconnected-(U14-CMN-Pad10)") (class "Default")
      (node (ref "U14") (pin "10") (pinfunction "CMN_10") (pintype "passive"))
    )
    (net (code "184") (name "unconnected-(U15-CMN-Pad10)") (class "Default")
      (node (ref "U15") (pin "10") (pinfunction "CMN_10") (pintype "passive"))
    )
    (net (code "185") (name "unconnected-(VR1-E-Pad3)") (class "Default")
      (node (ref "VR1") (pin "3") (pinfunction "E_3") (pintype "passive"))
    )
    (net (code "186") (name "unconnected-(VR2-E-Pad3)") (class "Default")
      (node (ref "VR2") (pin "3") (pinfunction "E_3") (pintype "passive"))
    )
    (net (code "187") (name "unconnected-(VR3-E-Pad3)") (class "Default")
      (node (ref "VR3") (pin "3") (pinfunction "E_3") (pintype "passive"))
    )
    (net (code "188") (name "unconnected-(VR4-E-Pad3)") (class "Default")
      (node (ref "VR4") (pin "3") (pinfunction "E_3") (pintype "passive"))
    )
    (net (code "189") (name "unconnected-(VR5-E-Pad3)") (class "Default")
      (node (ref "VR5") (pin "3") (pinfunction "E_3") (pintype "passive"))
    )
    (net (code "190") (name "unconnected-(VR6-E-Pad3)") (class "Default")
      (node (ref "VR6") (pin "3") (pinfunction "E_3") (pintype "passive"))
    )
    (net (code "191") (name "unconnected-(VR7-E-Pad3)") (class "Default")
      (node (ref "VR7") (pin "3") (pinfunction "E_3") (pintype "passive"))
    )
    (net (code "192") (name "unconnected-(VR8-E-Pad3)") (class "Default")
      (node (ref "VR8") (pin "3") (pinfunction "E_3") (pintype "passive"))
    )
  )
)
